# Fuente_Conn.net
KiCad netlist of a schematic drawn in Altium Designer
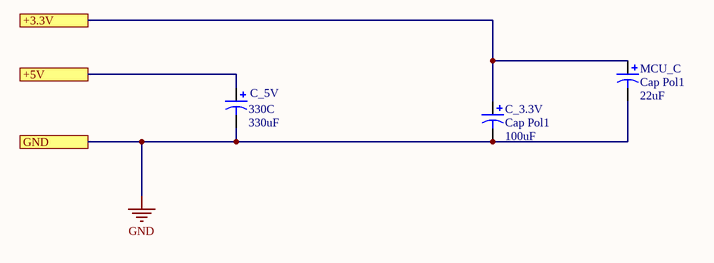
[diagram p0: Fuente_Conn.SchDoc]

(export (version "E")
  (design (tool "Eeschema 10.0.6"))
  (components
    (comp (ref "C_3.3V")
      (value "Cap Pol1")
      (footprint "CAPR5-4X5")
      (description "Polarized Capacitor (Radial)")
      (fields (field (name "ALTIUM_VALUE") "100uF") (field (name "PUBLISHER") "Altium Limited"))
      (libsource (lib "Miscellaneous Devices") (part "Cap Pol1"))
    )
    (comp (ref "C_5V")
      (value "330C")
      (footprint "PANASONIC_C")
      (description "Polarized Capacitor (Radial)")
      (fields (field (name "ALTIUM_VALUE") "330uF") (field (name "PUBLISHER") "Altium Limited"))
      (libsource (lib "Miscellaneous Devices") (part "Cap Pol1"))
    )
    (comp (ref "MCU_C")
      (value "Cap Pol1")
      (footprint "CAPR5-4X5")
      (description "Polarized Capacitor (Radial)")
      (fields (field (name "ALTIUM_VALUE") "22uF") (field (name "PUBLISHER") "Altium Limited"))
      (libsource (lib "Miscellaneous Devices") (part "Cap Pol1"))
    )
  )
  (nets
    (net (code "1") (name "/+3.3V") (class "Default")
      (node (ref "C_3.3V") (pin "1") (pinfunction "1_1") (pintype "passive"))
      (node (ref "MCU_C") (pin "1") (pinfunction "1_1") (pintype "passive"))
    )
    (net (code "2") (name "/+5V") (class "Default")
      (node (ref "C_5V") (pin "1") (pinfunction "1_1") (pintype "passive"))
    )
    (net (code "3") (name "GND") (class "Default")
      (node (ref "C_3.3V") (pin "2") (pinfunction "2_2") (pintype "passive"))
      (node (ref "C_5V") (pin "2") (pinfunction "2_2") (pintype "passive"))
      (node (ref "MCU_C") (pin "2") (pinfunction "2_2") (pintype "passive"))
    )
  )
)
